# VCO.net
KiCad netlist of a schematic drawn in Altium Designer
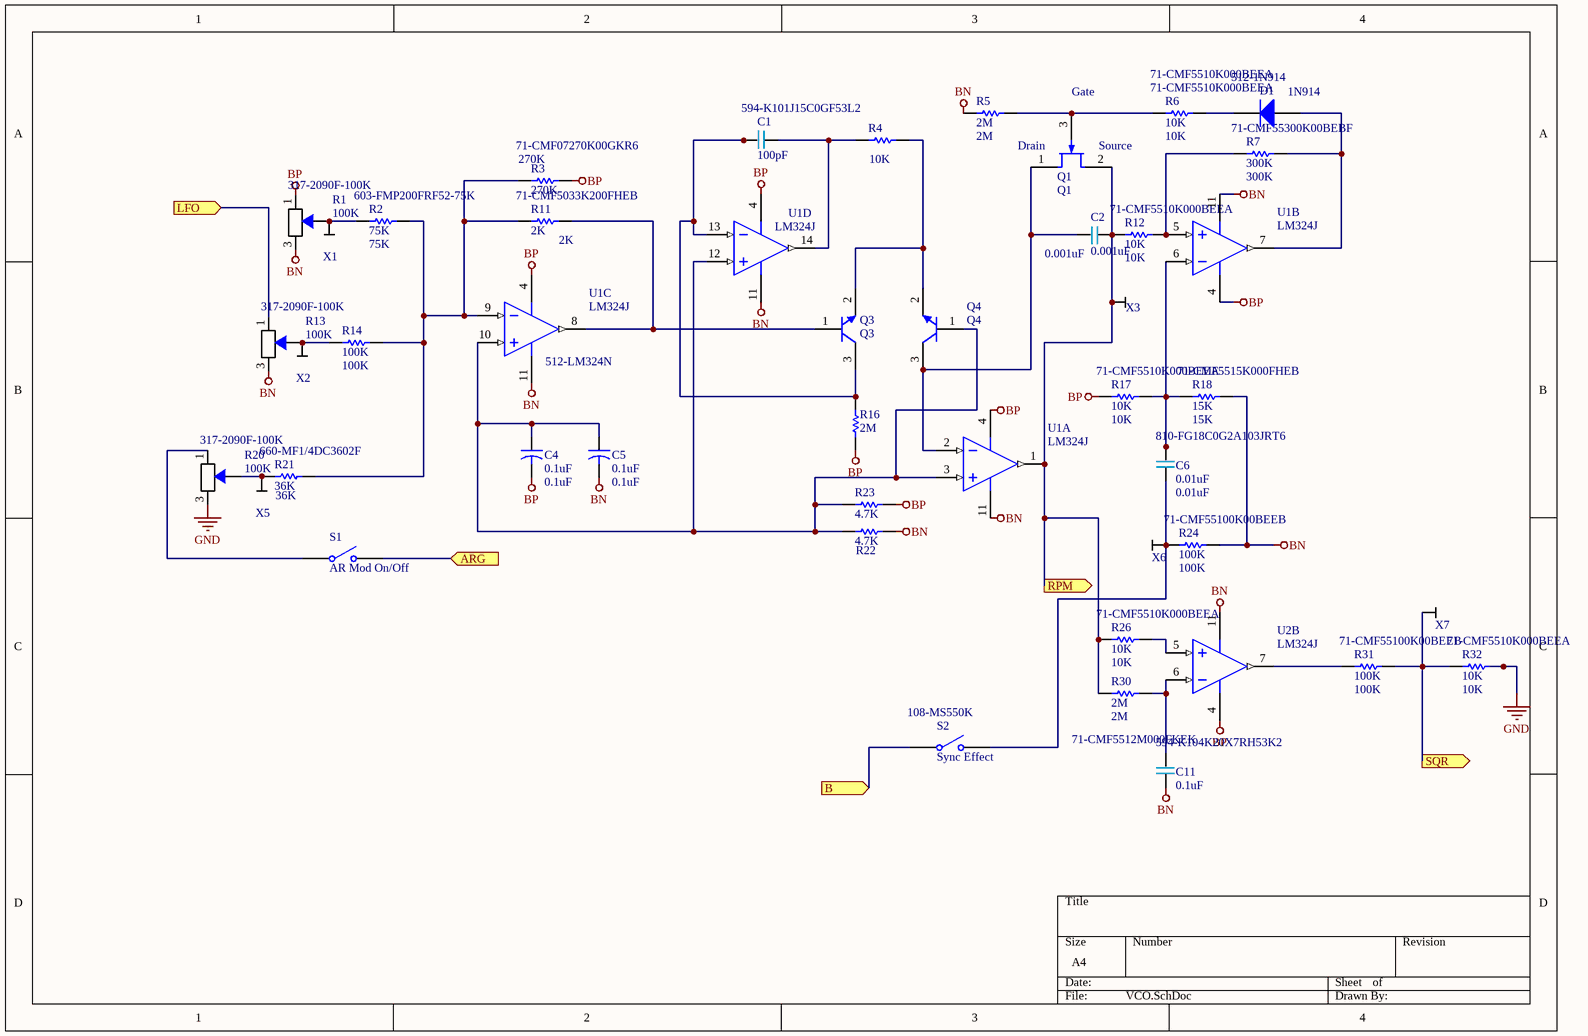
[diagram p0: VCO.SchDoc]

(export (version "E")
  (design (tool "Eeschema 10.0.6"))
  (components
    (comp (ref "C1")
      (value "100pF")
      (footprint "Cap Film 5")
      (fields
        (field (name "SUPPLIER PART NUMBER 1") "594-K101J15C0GF53L2")
        (field (name "MANUFACTURER") "Vishay / BC Components")
        (field (name "MANUFACTURER PART NUMBER") "K101J15C0GF53L2")
        (field (name "TOLERANCE") "5 %")
      )
      (libsource (lib "MyLibrary") (part "Cap Film 5"))
    )
    (comp (ref "C2")
      (value "0.001uF")
      (footprint "Cap Film 5")
      (fields (field (name "ALTIUM_VALUE") "0.001uF"))
      (libsource (lib "MyLibrary") (part "Cap Film 5"))
    )
    (comp (ref "C4")
      (value "0.1uF")
      (footprint "CAPR5-4X5")
      (description "Capacitor")
      (fields (field (name "ALTIUM_VALUE") "0.1uF") (field (name "PUBLISHER") "Altium Limited"))
      (libsource (lib "Miscellaneous Devices") (part "Cap2"))
    )
    (comp (ref "C5")
      (value "0.1uF")
      (footprint "CAPR5-4X5")
      (description "Capacitor")
      (fields (field (name "ALTIUM_VALUE") "0.1uF") (field (name "PUBLISHER") "Altium Limited"))
      (libsource (lib "Miscellaneous Devices") (part "Cap2"))
    )
    (comp (ref "C6")
      (value "0.01uF")
      (footprint "Cap Film 5")
      (fields
        (field (name "ALTIUM_VALUE") "0.01uF")
        (field (name "SUPPLIER PART NUMBER 1") "810-FG18C0G2A103JRT6")
        (field (name "MANUFACTURER") "TDK")
        (field (name "MANUFACTURER PART NUMBER") "FG18C0G2A103JRT06")
        (field (name "TOLERANCE") "5 %")
      )
      (libsource (lib "MyLibrary") (part "Cap Film 5"))
    )
    (comp (ref "C11")
      (value "0.1uF")
      (footprint "Cap Film 5")
      (fields
        (field (name "SUPPLIER PART NUMBER 1") "594-K104K20X7RH53K2")
        (field (name "MANUFACTURER") "Vishay / BC Components")
        (field (name "MANUFACTURER PART NUMBER") "K104K20X7RH53K2")
        (field (name "TOLERANCE") "10 %")
      )
      (libsource (lib "MyLibrary") (part "Cap Film 5"))
    )
    (comp (ref "D1")
      (value "1N914")
      (footprint "DO-35")
      (description "High Conductance Fast Diode")
      (fields (field (name "SUPPLIER PART NUMBER 1") "512-1N914") (field (name "PUBLISHER") "Altium Limited"))
      (libsource (lib "Miscellaneous Devices") (part "Diode 1N914"))
    )
    (comp (ref "Q1")
      (value "Q1")
      (footprint "ONSC-SOT-23-3-318-08_V")
      (description "JFET Switching Transistor, N-Channel, 3-Pin SOT-23, Tape and Reel")
      (fields (field (name "MANUFACTURER") "On Semiconductor") (field (name "PARTNUMBER") "MMBF4391LT1"))
      (libsource (lib "ON Semi JFETs") (part "MMBF4391LT1"))
    )
    (comp (ref "Q3")
      (value "Q3")
      (footprint "ONSC-SC-75-3-463-01_V")
      (description "General Purpose Transistor, NPN Silicon, 3-Pin SC-75, Pb-Free, Tape and Reel")
      (fields (field (name "MANUFACTURER") "On Semiconductor") (field (name "PARTNUMBER") "MMBT3904TT1G"))
      (libsource (lib "ON Semi General Purpose Transistors") (part "MMBT3904TT1G"))
    )
    (comp (ref "Q4")
      (value "Q4")
      (footprint "ONSC-SC-75-3-463-01_V")
      (description "General Purpose Transistor, NPN Silicon, 3-Pin SC-75, Pb-Free, Tape and Reel")
      (fields (field (name "MANUFACTURER") "On Semiconductor") (field (name "PARTNUMBER") "MMBT3904TT1G"))
      (libsource (lib "ON Semi General Purpose Transistors") (part "MMBT3904TT1G"))
    )
    (comp (ref "R1")
      (value "100K")
      (footprint "Potentiometer")
      (description "My Own")
      (fields
        (field (name "SUPPLIER PART NUMBER 1") "317-2090F-100K")
        (field (name "MANUFACTURER") "Alpha (Taiwan)")
        (field (name "MANUFACTURER PART NUMBER") "RV09AF-40-20K-B100K")
      )
      (libsource (lib "MyLibrary") (part "Potentiometer"))
    )
    (comp (ref "R2")
      (value "75K")
      (footprint "AXIAL-0.3")
      (description "Resistor")
      (fields
        (field (name "ALTIUM_VALUE") "75K")
        (field (name "SUPPLIER PART NUMBER 1") "603-FMP200FRF52-75K")
        (field (name "MANUFACTURER") "Yageo")
        (field (name "MANUFACTURER PART NUMBER") "FMP200FRF52-75K")
        (field (name "PUBLISHER") "Altium Limited")
      )
      (libsource (lib "Miscellaneous Devices") (part "Res1"))
    )
    (comp (ref "R3")
      (value "270K")
      (footprint "AXIAL-0.3")
      (description "Resistor")
      (fields
        (field (name "ALTIUM_VALUE") "270K")
        (field (name "SUPPLIER PART NUMBER 1") "71-CMF07270K00GKR6")
        (field (name "MANUFACTURER") "Vishay / Dale")
        (field (name "MANUFACTURER PART NUMBER") "CMF07270K00GKR6")
        (field (name "PUBLISHER") "Altium Limited")
      )
      (libsource (lib "Miscellaneous Devices") (part "Res1"))
    )
    (comp (ref "R4")
      (value "10K")
      (footprint "AXIAL-0.3")
      (description "Metal Film Resistors - Through Hole 1/4watt 10Kohms 5% Rated to 1/2watt")
      (fields
        (field (name "MANUFACTURER") "Vishay / Dale")
        (field (name "MANUFACTURER PART NUMBER") "CCF0710K0JKE36")
        (field (name "PUBLISHER") "Altium Limited")
      )
      (libsource (lib "Miscellaneous Devices") (part "Res1"))
    )
    (comp (ref "R5")
      (value "2M")
      (footprint "AXIAL-0.3")
      (description "Resistor")
      (fields
        (field (name "ALTIUM_VALUE") "2M")
        (field (name "MANUFACTURER PART NUMBER") "CMF5512M000FKEK")
        (field (name "PUBLISHER") "Altium Limited")
      )
      (libsource (lib "Miscellaneous Devices") (part "Res1"))
    )
    (comp (ref "R6")
      (value "10K")
      (footprint "AXIAL-0.3")
      (description "Resistor")
      (fields
        (field (name "ALTIUM_VALUE") "10K")
        (field (name "SUPPLIER PART NUMBER 1") "71-CMF5510K000BEEA")
        (field (name "MANUFACTURER") "Vishay / Dale")
        (field (name "MANUFACTURER PART NUMBER") "CCF0710K0JKE36")
        (field (name "SUPPLIER PART NUMBER 2") "71-CMF5510K000BEEA")
        (field (name "PUBLISHER") "Altium Limited")
      )
      (libsource (lib "Miscellaneous Devices") (part "Res1"))
    )
    (comp (ref "R7")
      (value "300K")
      (footprint "AXIAL-0.3")
      (description "Resistor")
      (fields
        (field (name "ALTIUM_VALUE") "300K")
        (field (name "SUPPLIER PART NUMBER 1") "71-CMF55300K00BEBF")
        (field (name "MANUFACTURER") "Vishay / Dale")
        (field (name "MANUFACTURER PART NUMBER") "CMF55300K00BEBF")
        (field (name "PUBLISHER") "Altium Limited")
      )
      (libsource (lib "Miscellaneous Devices") (part "Res1"))
    )
    (comp (ref "R11")
      (value "2K")
      (footprint "AXIAL-0.3")
      (description "Resistor")
      (fields
        (field (name "ALTIUM_VALUE") "2K")
        (field (name "SUPPLIER PART NUMBER 1") "71-CMF5033K200FHEB")
        (field (name "MANUFACTURER") "Vishay / Dale")
        (field (name "MANUFACTURER PART NUMBER") "CMF5033K200FHEB")
        (field (name "PUBLISHER") "Altium Limited")
      )
      (libsource (lib "Miscellaneous Devices") (part "Res1"))
    )
    (comp (ref "R12")
      (value "10K")
      (footprint "AXIAL-0.3")
      (description "Metal Film Resistors - Through Hole 1/4watt 10Kohms 5% Rated to 1/2watt")
      (fields
        (field (name "ALTIUM_VALUE") "10K")
        (field (name "MANUFACTURER") "Vishay / Dale")
        (field (name "MANUFACTURER PART NUMBER") "CCF0710K0JKE36")
        (field (name "SUPPLIER PART NUMBER 2") "71-CMF5510K000BEEA")
        (field (name "PUBLISHER") "Altium Limited")
      )
      (libsource (lib "Miscellaneous Devices") (part "Res1"))
    )
    (comp (ref "R13")
      (value "100K")
      (footprint "Potentiometer")
      (description "My Own")
      (fields
        (field (name "SUPPLIER PART NUMBER 1") "317-2090F-100K")
        (field (name "MANUFACTURER") "Alpha (Taiwan)")
        (field (name "MANUFACTURER PART NUMBER") "RV09AF-40-20K-B100K")
      )
      (libsource (lib "MyLibrary") (part "Potentiometer"))
    )
    (comp (ref "R14")
      (value "100K")
      (footprint "AXIAL-0.3")
      (description "Resistor")
      (fields
        (field (name "ALTIUM_VALUE") "100K")
        (field (name "MANUFACTURER") "Vishay / Dale")
        (field (name "MANUFACTURER PART NUMBER") "CMF55100K00FHEK")
        (field (name "PUBLISHER") "Altium Limited")
      )
      (libsource (lib "Miscellaneous Devices") (part "Res1"))
    )
    (comp (ref "R16")
      (value "2M")
      (footprint "AXIAL-0.3")
      (description "Resistor")
      (fields
        (field (name "MANUFACTURER PART NUMBER") "CMF5512M000FKEK")
        (field (name "PUBLISHER") "Altium Limited")
      )
      (libsource (lib "Miscellaneous Devices") (part "Res1"))
    )
    (comp (ref "R17")
      (value "10K")
      (footprint "AXIAL-0.3")
      (description "Metal Film Resistors - Through Hole 1/4watt 10Kohms 5% Rated to 1/2watt")
      (fields
        (field (name "ALTIUM_VALUE") "10K")
        (field (name "MANUFACTURER") "Vishay / Dale")
        (field (name "MANUFACTURER PART NUMBER") "CCF0710K0JKE36")
        (field (name "SUPPLIER PART NUMBER 2") "71-CMF5510K000BEEA")
        (field (name "PUBLISHER") "Altium Limited")
      )
      (libsource (lib "Miscellaneous Devices") (part "Res1"))
    )
    (comp (ref "R18")
      (value "15K")
      (footprint "AXIAL-0.3")
      (description "Resistor")
      (fields
        (field (name "ALTIUM_VALUE") "15K")
        (field (name "SUPPLIER PART NUMBER 1") "71-CMF5515K000FHEB")
        (field (name "MANUFACTURER") "Vishay / Dale")
        (field (name "MANUFACTURER PART NUMBER") "CMF5515K000FHEB")
        (field (name "PUBLISHER") "Altium Limited")
      )
      (libsource (lib "Miscellaneous Devices") (part "Res1"))
    )
    (comp (ref "R20")
      (value "100K")
      (footprint "Potentiometer")
      (description "My Own")
      (fields
        (field (name "SUPPLIER PART NUMBER 1") "317-2090F-100K")
        (field (name "MANUFACTURER") "Alpha (Taiwan)")
        (field (name "MANUFACTURER PART NUMBER") "RV09AF-40-20K-B100K")
      )
      (libsource (lib "MyLibrary") (part "Potentiometer"))
    )
    (comp (ref "R21")
      (value "36K")
      (footprint "AXIAL-0.3")
      (description "Resistor")
      (fields
        (field (name "ALTIUM_VALUE") "36K")
        (field (name "SUPPLIER PART NUMBER 1") "660-MF1/4DC3602F")
        (field (name "MANUFACTURER") "KOA Speer")
        (field (name "MANUFACTURER PART NUMBER") "MF1/4DC3602F")
        (field (name "PUBLISHER") "Altium Limited")
      )
      (libsource (lib "Miscellaneous Devices") (part "Res1"))
    )
    (comp (ref "R22")
      (value "4.7K")
      (footprint "AXIAL-0.3")
      (description "Resistor")
      (fields
        (field (name "MANUFACTURER") "Vishay / Dale")
        (field (name "MANUFACTURER PART NUMBER") "CCF074K70JKE36")
        (field (name "PUBLISHER") "Altium Limited")
      )
      (libsource (lib "Miscellaneous Devices") (part "Res1"))
    )
    (comp (ref "R23")
      (value "4.7K")
      (footprint "AXIAL-0.3")
      (description "Resistor")
      (fields
        (field (name "MANUFACTURER") "Vishay / Dale")
        (field (name "MANUFACTURER PART NUMBER") "CCF074K70JKE36")
        (field (name "PUBLISHER") "Altium Limited")
      )
      (libsource (lib "Miscellaneous Devices") (part "Res1"))
    )
    (comp (ref "R24")
      (value "100K")
      (footprint "AXIAL-0.3")
      (description "Resistor")
      (fields
        (field (name "ALTIUM_VALUE") "100K")
        (field (name "MANUFACTURER") "Vishay / Dale")
        (field (name "MANUFACTURER PART NUMBER") "CMF55100K00FHEK")
        (field (name "SUPPLIER PART NUMBER 2") "71-CMF55100K00BEEB")
        (field (name "PUBLISHER") "Altium Limited")
      )
      (libsource (lib "Miscellaneous Devices") (part "Res1"))
    )
    (comp (ref "R26")
      (value "10K")
      (footprint "AXIAL-0.3")
      (description "Metal Film Resistors - Through Hole 1/4watt 10Kohms 5% Rated to 1/2watt")
      (fields
        (field (name "ALTIUM_VALUE") "10K")
        (field (name "MANUFACTURER") "Vishay / Dale")
        (field (name "MANUFACTURER PART NUMBER") "CCF0710K0JKE36")
        (field (name "SUPPLIER PART NUMBER 2") "71-CMF5510K000BEEA")
        (field (name "PUBLISHER") "Altium Limited")
      )
      (libsource (lib "Miscellaneous Devices") (part "Res1"))
    )
    (comp (ref "R30")
      (value "2M")
      (footprint "AXIAL-0.3")
      (description "Resistor")
      (fields
        (field (name "ALTIUM_VALUE") "2M")
        (field (name "SUPPLIER PART NUMBER 1") "71-CMF5512M000FKEK")
        (field (name "MANUFACTURER") "Vishay / Dale")
        (field (name "MANUFACTURER PART NUMBER") "CMF5512M000FKEK")
        (field (name "PUBLISHER") "Altium Limited")
      )
      (libsource (lib "Miscellaneous Devices") (part "Res1"))
    )
    (comp (ref "R31")
      (value "100K")
      (footprint "AXIAL-0.3")
      (description "Resistor")
      (fields
        (field (name "ALTIUM_VALUE") "100K")
        (field (name "MANUFACTURER") "Vishay / Dale")
        (field (name "MANUFACTURER PART NUMBER") "CMF55100K00FHEK")
        (field (name "SUPPLIER PART NUMBER 2") "71-CMF55100K00BEEB")
        (field (name "PUBLISHER") "Altium Limited")
      )
      (libsource (lib "Miscellaneous Devices") (part "Res1"))
    )
    (comp (ref "R32")
      (value "10K")
      (footprint "AXIAL-0.3")
      (description "Metal Film Resistors - Through Hole 1/4watt 10Kohms 5% Rated to 1/2watt")
      (fields
        (field (name "ALTIUM_VALUE") "10K")
        (field (name "MANUFACTURER") "Vishay / Dale")
        (field (name "MANUFACTURER PART NUMBER") "CCF0710K0JKE36")
        (field (name "SUPPLIER PART NUMBER 2") "71-CMF5510K000BEEA")
        (field (name "PUBLISHER") "Altium Limited")
      )
      (libsource (lib "Miscellaneous Devices") (part "Res1"))
    )
    (comp (ref "S1")
      (value "AR Mod On/Off")
      (footprint "SPST-2")
      (description "Single-Pole, Single-Throw Switch")
      (fields (field (name "PUBLISHER") "Altium Limited"))
      (libsource (lib "Miscellaneous Devices") (part "SW-SPST"))
    )
    (comp (ref "S2")
      (value "Sync Effect")
      (footprint "SPST-2")
      (description "Single-Pole, Single-Throw Switch")
      (fields
        (field (name "SUPPLIER PART NUMBER 1") "108-MS550K")
        (field (name "MANUFACTURER") "Mountain Switch")
        (field (name "MANUFACTURER PART NUMBER") "108-MS550K")
        (field (name "PUBLISHER") "Altium Limited")
      )
      (libsource (lib "Miscellaneous Devices") (part "SW-SPST"))
    )
    (comp (ref "U1")
      (value "LM324J")
      (footprint "J14A")
      (description "Low Power Quad Operational Amplifier, 14-pin CerDIP")
      (fields
        (field (name "MANUFACTURER") "National Semiconductor")
        (field (name "SUPPLIER PART NUMBER 1") "512-LM324N")
        (field (name "MANUFACTURER PART NUMBER") "LM324N")
      )
      (libsource (lib "National Semiconductor Amplifier") (part "LM324J"))
    )
    (comp (ref "U2")
      (value "LM324J")
      (footprint "J14A")
      (description "Low Power Quad Operational Amplifier, 14-pin CerDIP")
      (fields (field (name "MANUFACTURER") "National Semiconductor"))
      (libsource (lib "National Semiconductor Amplifier") (part "LM324J"))
    )
    (comp (ref "X1") (value "X1") (footprint "Pad") (libsource (lib "MyLibrary") (part "Pad")))
    (comp (ref "X2") (value "X2") (footprint "Pad") (libsource (lib "MyLibrary") (part "Pad")))
    (comp (ref "X3") (value "X3") (footprint "Pad") (libsource (lib "MyLibrary") (part "Pad")))
    (comp (ref "X5") (value "Pad") (footprint "Pad") (libsource (lib "MyLibrary") (part "Pad")))
    (comp (ref "X6") (value "X6") (footprint "Pad") (libsource (lib "MyLibrary") (part "Pad")))
    (comp (ref "X7") (value "X7") (footprint "Pad") (libsource (lib "MyLibrary") (part "Pad")))
  )
  (nets
    (net (code "1") (name "/ARG") (class "Default")
      (node (ref "S1") (pin "2") (pinfunction "NO_2") (pintype "passive"))
    )
    (net (code "2") (name "/B") (class "Default")
      (node (ref "S2") (pin "1") (pinfunction "COMMON_1") (pintype "passive"))
    )
    (net (code "3") (name "/LFO") (class "Default")
      (node (ref "R13") (pin "1") (pinfunction "1_1") (pintype "passive"))
    )
    (net (code "4") (name "/RPM") (class "Default")
      (node (ref "C2") (pin "1") (pinfunction "1_1") (pintype "passive"))
      (node (ref "Q1") (pin "2") (pinfunction "S_2") (pintype "passive"))
      (node (ref "R12") (pin "1") (pinfunction "1_1") (pintype "passive"))
      (node (ref "R26") (pin "1") (pinfunction "1_1") (pintype "passive"))
      (node (ref "R30") (pin "1") (pinfunction "1_1") (pintype "passive"))
      (node (ref "U1") (pin "1") (pinfunction "OUT1_1") (pintype "output"))
      (node (ref "X3") (pin "1") (pinfunction "1_1") (pintype "passive"))
    )
    (net (code "5") (name "/SQR") (class "Default")
      (node (ref "R31") (pin "2") (pinfunction "2_2") (pintype "passive"))
      (node (ref "R32") (pin "1") (pinfunction "1_1") (pintype "passive"))
      (node (ref "X7") (pin "1") (pinfunction "1_1") (pintype "passive"))
    )
    (net (code "6") (name "BN") (class "Default")
      (node (ref "C11") (pin "1") (pinfunction "1_1") (pintype "passive"))
      (node (ref "C5") (pin "2") (pinfunction "2_2") (pintype "passive"))
      (node (ref "R1") (pin "3") (pinfunction "3_3") (pintype "passive"))
      (node (ref "R13") (pin "3") (pinfunction "3_3") (pintype "passive"))
      (node (ref "R18") (pin "2") (pinfunction "2_2") (pintype "passive"))
      (node (ref "R22") (pin "1") (pinfunction "1_1") (pintype "passive"))
      (node (ref "R24") (pin "2") (pinfunction "2_2") (pintype "passive"))
      (node (ref "R5") (pin "1") (pinfunction "1_1") (pintype "passive"))
      (node (ref "U1") (pin "11") (pinfunction "GND_11") (pintype "power_in"))
      (node (ref "U2") (pin "11") (pinfunction "GND_11") (pintype "power_in"))
    )
    (net (code "7") (name "BP") (class "Default")
      (node (ref "C4") (pin "2") (pinfunction "2_2") (pintype "passive"))
      (node (ref "R1") (pin "1") (pinfunction "1_1") (pintype "passive"))
      (node (ref "R16") (pin "1") (pinfunction "1_1") (pintype "passive"))
      (node (ref "R17") (pin "1") (pinfunction "1_1") (pintype "passive"))
      (node (ref "R23") (pin "1") (pinfunction "1_1") (pintype "passive"))
      (node (ref "R3") (pin "2") (pinfunction "2_2") (pintype "passive"))
      (node (ref "U1") (pin "4") (pinfunction "V+_4") (pintype "power_in"))
      (node (ref "U2") (pin "4") (pinfunction "V+_4") (pintype "power_in"))
    )
    (net (code "8") (name "GND") (class "Default")
      (node (ref "R20") (pin "3") (pinfunction "3_3") (pintype "passive"))
      (node (ref "R32") (pin "2") (pinfunction "2_2") (pintype "passive"))
    )
    (net (code "9") (name "Net-(D1-A)") (class "Default")
      (node (ref "D1") (pin "1") (pinfunction "A_1") (pintype "passive"))
      (node (ref "R7") (pin "2") (pinfunction "2_2") (pintype "passive"))
      (node (ref "U1") (pin "7") (pinfunction "OUT2_7") (pintype "output"))
    )
    (net (code "10") (name "Net-(D1-K)") (class "Default")
      (node (ref "D1") (pin "2") (pinfunction "K_2") (pintype "passive"))
      (node (ref "R6") (pin "2") (pinfunction "2_2") (pintype "passive"))
    )
    (net (code "11") (name "Net-(Q1-D)") (class "Default")
      (node (ref "C2") (pin "2") (pinfunction "2_2") (pintype "passive"))
      (node (ref "Q1") (pin "1") (pinfunction "D_1") (pintype "passive"))
      (node (ref "Q4") (pin "3") (pinfunction "C_3") (pintype "passive"))
      (node (ref "U1") (pin "2") (pinfunction "IN1-_2") (pintype "input"))
    )
    (net (code "12") (name "Net-(Q1-G)") (class "Default")
      (node (ref "Q1") (pin "3") (pinfunction "G_3") (pintype "passive"))
      (node (ref "R5") (pin "2") (pinfunction "2_2") (pintype "passive"))
      (node (ref "R6") (pin "1") (pinfunction "1_1") (pintype "passive"))
    )
    (net (code "13") (name "Net-(Q3-B)") (class "Default")
      (node (ref "Q3") (pin "1") (pinfunction "B_1") (pintype "passive"))
      (node (ref "R11") (pin "2") (pinfunction "2_2") (pintype "passive"))
      (node (ref "U1") (pin "8") (pinfunction "OUT3_8") (pintype "output"))
    )
    (net (code "14") (name "Net-(Q3-C)") (class "Default")
      (node (ref "C1") (pin "1") (pinfunction "1_1") (pintype "passive"))
      (node (ref "Q3") (pin "3") (pinfunction "C_3") (pintype "passive"))
      (node (ref "R16") (pin "2") (pinfunction "2_2") (pintype "passive"))
      (node (ref "U1") (pin "13") (pinfunction "IN4-_13") (pintype "input"))
    )
    (net (code "15") (name "Net-(Q3-E)") (class "Default")
      (node (ref "Q3") (pin "2") (pinfunction "E_2") (pintype "passive"))
      (node (ref "Q4") (pin "2") (pinfunction "E_2") (pintype "passive"))
      (node (ref "R4") (pin "2") (pinfunction "2_2") (pintype "passive"))
    )
    (net (code "16") (name "Net-(Q4-B)") (class "Default")
      (node (ref "C4") (pin "1") (pinfunction "1_1") (pintype "passive"))
      (node (ref "C5") (pin "1") (pinfunction "1_1") (pintype "passive"))
      (node (ref "Q4") (pin "1") (pinfunction "B_1") (pintype "passive"))
      (node (ref "R22") (pin "2") (pinfunction "2_2") (pintype "passive"))
      (node (ref "R23") (pin "2") (pinfunction "2_2") (pintype "passive"))
      (node (ref "U1") (pin "10") (pinfunction "IN3+_10") (pintype "input"))
      (node (ref "U1") (pin "12") (pinfunction "IN4+_12") (pintype "input"))
      (node (ref "U1") (pin "3") (pinfunction "IN1+_3") (pintype "input"))
    )
    (net (code "17") (name "Net-(R1-Pad2)") (class "Default")
      (node (ref "R1") (pin "2") (pinfunction "2_2") (pintype "passive"))
      (node (ref "R2") (pin "1") (pinfunction "1_1") (pintype "passive"))
      (node (ref "X1") (pin "1") (pinfunction "1_1") (pintype "passive"))
    )
    (net (code "18") (name "Net-(R13-Pad2)") (class "Default")
      (node (ref "R13") (pin "2") (pinfunction "2_2") (pintype "passive"))
      (node (ref "R14") (pin "1") (pinfunction "1_1") (pintype "passive"))
      (node (ref "X2") (pin "1") (pinfunction "1_1") (pintype "passive"))
    )
    (net (code "19") (name "Net-(R20-Pad2)") (class "Default")
      (node (ref "R20") (pin "2") (pinfunction "2_2") (pintype "passive"))
      (node (ref "R21") (pin "1") (pinfunction "1_1") (pintype "passive"))
      (node (ref "X5") (pin "1") (pinfunction "1_1") (pintype "passive"))
    )
    (net (code "20") (name "Net-(S1-COMMON)") (class "Default")
      (node (ref "R20") (pin "1") (pinfunction "1_1") (pintype "passive"))
      (node (ref "S1") (pin "1") (pinfunction "COMMON_1") (pintype "passive"))
    )
    (net (code "21") (name "Net-(S2-NO)") (class "Default")
      (node (ref "C6") (pin "1") (pinfunction "1_1") (pintype "passive"))
      (node (ref "R24") (pin "1") (pinfunction "1_1") (pintype "passive"))
      (node (ref "S2") (pin "2") (pinfunction "NO_2") (pintype "passive"))
      (node (ref "X6") (pin "1") (pinfunction "1_1") (pintype "passive"))
    )
    (net (code "22") (name "Net-(U1B-IN2+)") (class "Default")
      (node (ref "R12") (pin "2") (pinfunction "2_2") (pintype "passive"))
      (node (ref "R7") (pin "1") (pinfunction "1_1") (pintype "passive"))
      (node (ref "U1") (pin "5") (pinfunction "IN2+_5") (pintype "input"))
    )
    (net (code "23") (name "Net-(U1B-IN2-)") (class "Default")
      (node (ref "C6") (pin "2") (pinfunction "2_2") (pintype "passive"))
      (node (ref "R17") (pin "2") (pinfunction "2_2") (pintype "passive"))
      (node (ref "R18") (pin "1") (pinfunction "1_1") (pintype "passive"))
      (node (ref "U1") (pin "6") (pinfunction "IN2-_6") (pintype "input"))
    )
    (net (code "24") (name "Net-(U1C-IN3-)") (class "Default")
      (node (ref "R11") (pin "1") (pinfunction "1_1") (pintype "passive"))
      (node (ref "R14") (pin "2") (pinfunction "2_2") (pintype "passive"))
      (node (ref "R2") (pin "2") (pinfunction "2_2") (pintype "passive"))
      (node (ref "R21") (pin "2") (pinfunction "2_2") (pintype "passive"))
      (node (ref "R3") (pin "1") (pinfunction "1_1") (pintype "passive"))
      (node (ref "U1") (pin "9") (pinfunction "IN3-_9") (pintype "input"))
    )
    (net (code "25") (name "Net-(U1D-OUT4)") (class "Default")
      (node (ref "C1") (pin "2") (pinfunction "2_2") (pintype "passive"))
      (node (ref "R4") (pin "1") (pinfunction "1_1") (pintype "passive"))
      (node (ref "U1") (pin "14") (pinfunction "OUT4_14") (pintype "output"))
    )
    (net (code "26") (name "Net-(U2B-IN2+)") (class "Default")
      (node (ref "R26") (pin "2") (pinfunction "2_2") (pintype "passive"))
      (node (ref "U2") (pin "5") (pinfunction "IN2+_5") (pintype "input"))
    )
    (net (code "27") (name "Net-(U2B-IN2-)") (class "Default")
      (node (ref "C11") (pin "2") (pinfunction "2_2") (pintype "passive"))
      (node (ref "R30") (pin "2") (pinfunction "2_2") (pintype "passive"))
      (node (ref "U2") (pin "6") (pinfunction "IN2-_6") (pintype "input"))
    )
    (net (code "28") (name "Net-(U2B-OUT2)") (class "Default")
      (node (ref "R31") (pin "1") (pinfunction "1_1") (pintype "passive"))
      (node (ref "U2") (pin "7") (pinfunction "OUT2_7") (pintype "output"))
    )
  )
)
